# MicroSD.net
KiCad netlist of a schematic drawn in Altium Designer
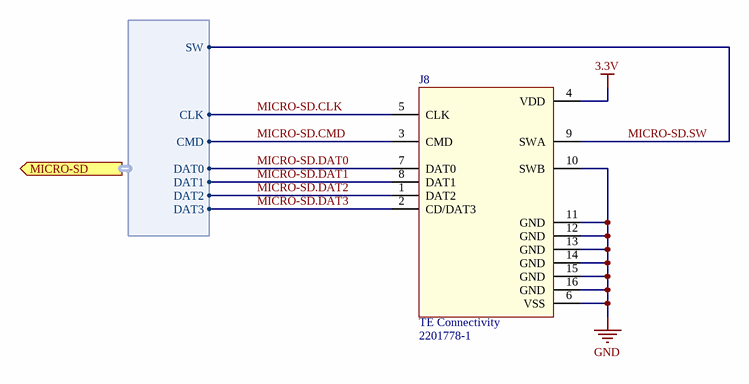
[diagram p0: MicroSD.SchDoc]

(export (version "E")
  (design (tool "Eeschema 10.0.6"))
  (components
    (comp (ref "J8")
      (value "2201778-1")
      (footprint "TE-2201778-1")
      (description "Conn Memory Card RCP 8 POS 1.1mm Solder RA SMD 0.5A/Contact T/R")
      (fields (field (name "MANUFACTURER") "TE Connectivity") (field (name "PARTNUMBER") "2201778-1"))
      (libsource (lib "TeConnectivity") (part "2201778-1"))
    )
  )
  (nets
    (net (code "2") (name "/MICRO-SD.CLK") (class "Default")
      (node (ref "J8") (pin "5") (pinfunction "CLK_5") (pintype "power_in"))
    )
    (net (code "3") (name "/MICRO-SD.CMD") (class "Default")
      (node (ref "J8") (pin "3") (pinfunction "CMD_3") (pintype "power_in"))
    )
    (net (code "4") (name "/MICRO-SD.DAT0") (class "Default")
      (node (ref "J8") (pin "7") (pinfunction "DAT0_7") (pintype "power_in"))
    )
    (net (code "5") (name "/MICRO-SD.DAT1") (class "Default")
      (node (ref "J8") (pin "8") (pinfunction "DAT1_8") (pintype "power_in"))
    )
    (net (code "6") (name "/MICRO-SD.DAT2") (class "Default")
      (node (ref "J8") (pin "1") (pinfunction "DAT2_1") (pintype "power_in"))
    )
    (net (code "7") (name "/MICRO-SD.DAT3") (class "Default")
      (node (ref "J8") (pin "2") (pinfunction "CD/DAT3_2") (pintype "power_in"))
    )
    (net (code "8") (name "/MICRO-SD.SW") (class "Default")
      (node (ref "J8") (pin "9") (pinfunction "SWA_9") (pintype "passive"))
    )
    (net (code "10") (name "3.3V") (class "Default")
      (node (ref "J8") (pin "4") (pinfunction "VDD_4") (pintype "power_in"))
    )
    (net (code "11") (name "GND") (class "Default")
      (node (ref "J8") (pin "10") (pinfunction "SWB_10") (pintype "passive"))
      (node (ref "J8") (pin "11") (pinfunction "GND_11") (pintype "power_in"))
      (node (ref "J8") (pin "12") (pinfunction "GND_12") (pintype "power_in"))
      (node (ref "J8") (pin "13") (pinfunction "GND_13") (pintype "power_in"))
      (node (ref "J8") (pin "14") (pinfunction "GND_14") (pintype "power_in"))
      (node (ref "J8") (pin "15") (pinfunction "GND_15") (pintype "power_in"))
      (node (ref "J8") (pin "16") (pinfunction "GND_16") (pintype "power_in"))
      (node (ref "J8") (pin "6") (pinfunction "VSS_6") (pintype "power_in"))
    )
  )
)
